# Gameboy_Cartridge.net
KiCad netlist of a schematic drawn in EAGLE
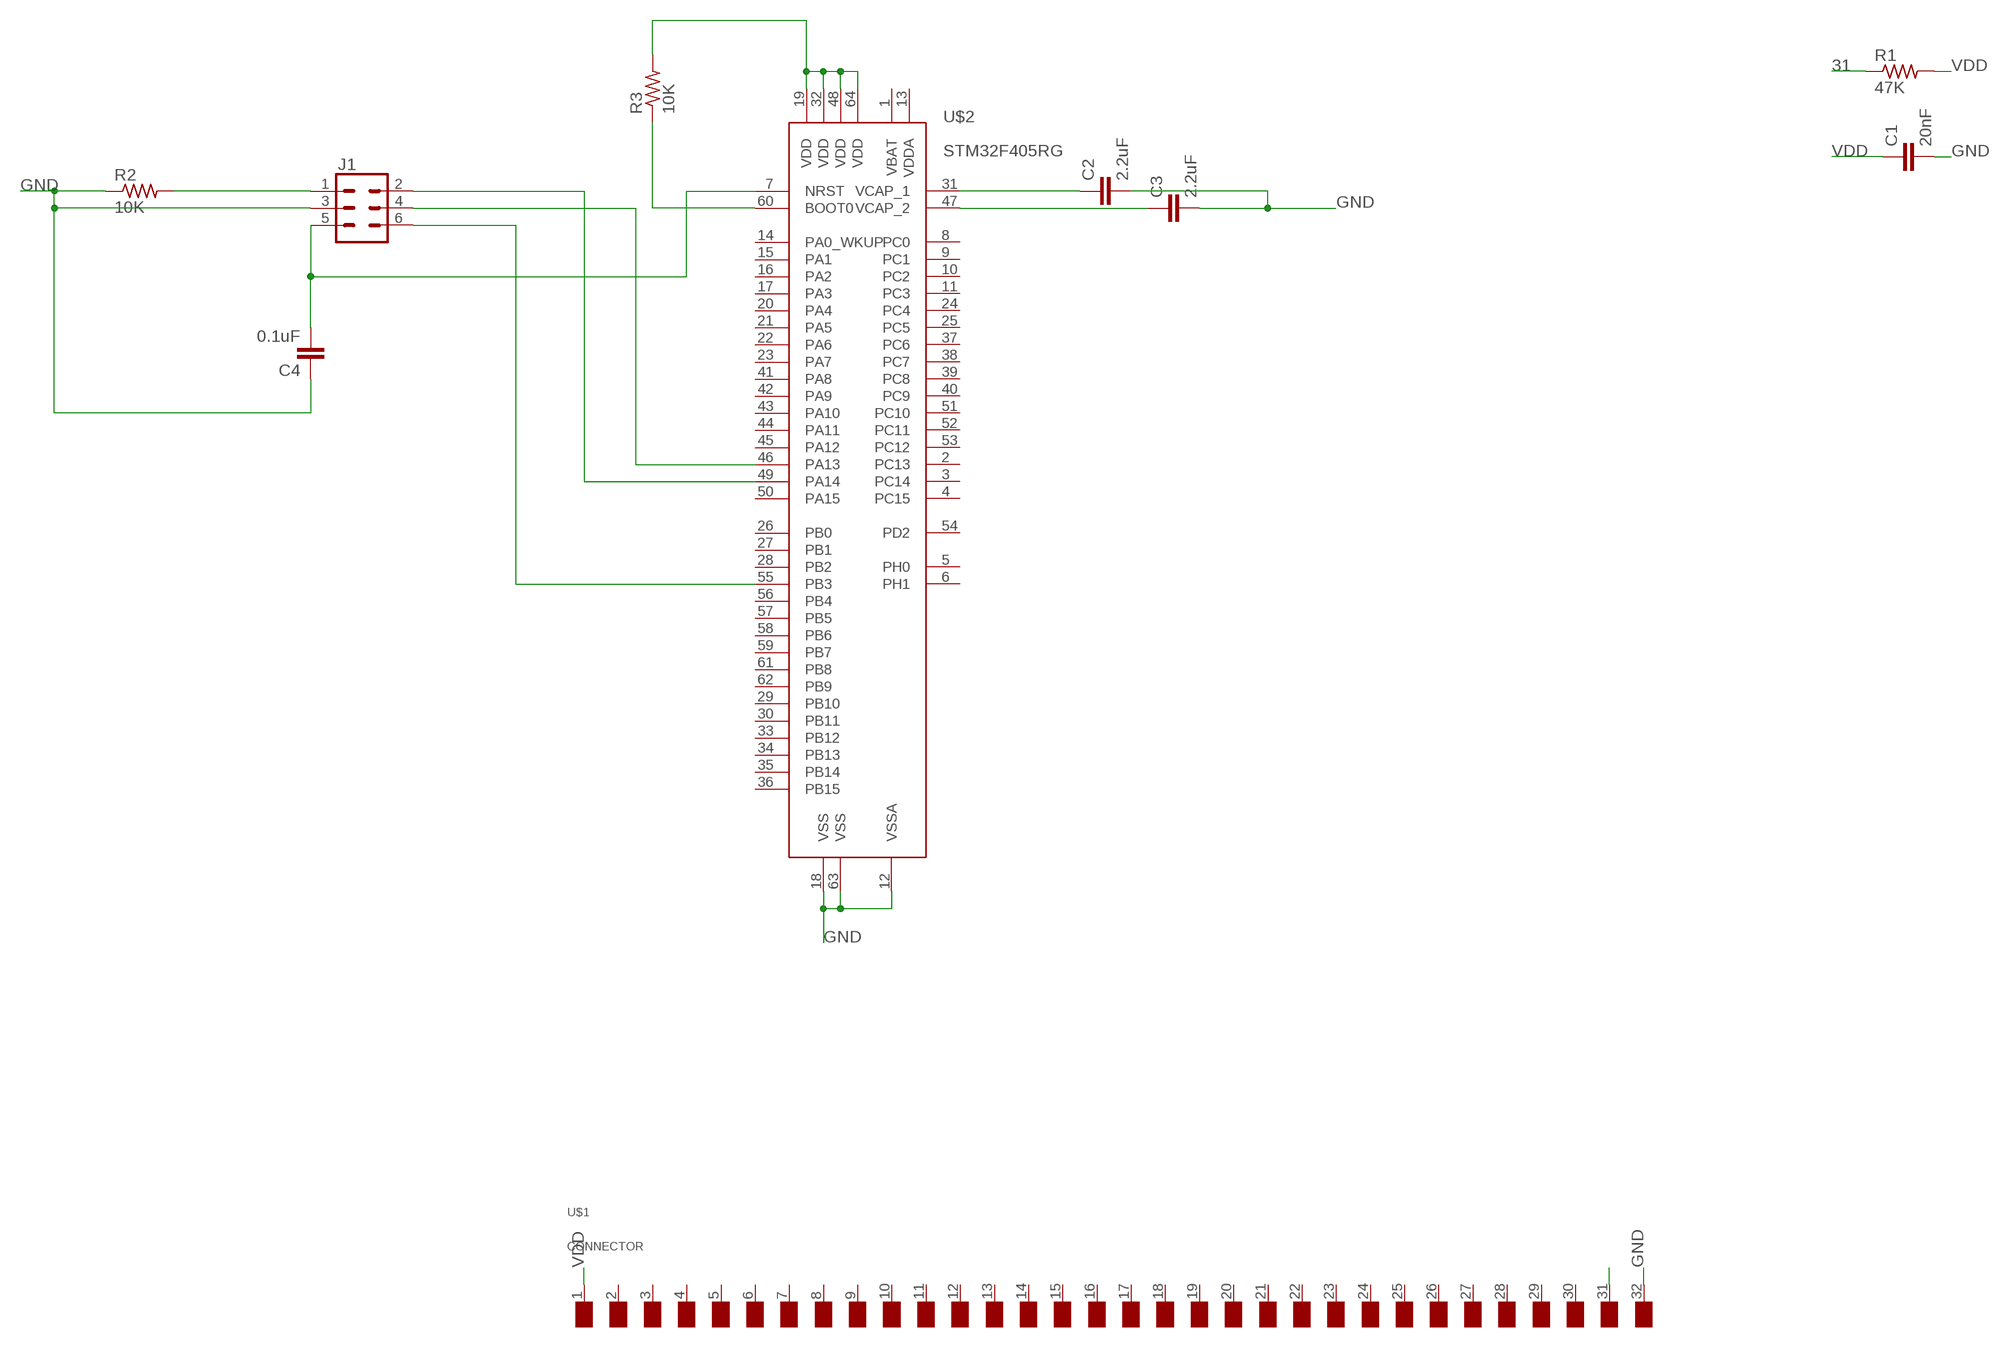
[diagram p0: schematic, sheet 1]

(export (version "E")
  (design (tool "Eeschema 10.0.6"))
  (components
    (comp (ref "C1")
      (value "20nF")
      (footprint "eagle-import:C0805")
      (libsource (lib "eagle-import") (part "C-EUC0805"))
    )
    (comp (ref "C2")
      (value "2.2uF")
      (footprint "eagle-import:C0805")
      (libsource (lib "eagle-import") (part "C-EUC0805"))
    )
    (comp (ref "C3")
      (value "2.2uF")
      (footprint "eagle-import:C0805")
      (libsource (lib "eagle-import") (part "C-EUC0805"))
    )
    (comp (ref "C4")
      (value "0.1uF")
      (footprint "eagle-import:C0805")
      (libsource (lib "eagle-import") (part "C-EUC0805"))
    )
    (comp (ref "J1")
      (value "CONN_03X2FEMALE_SMD")
      (footprint "eagle-import:2X3_SMD")
      (libsource (lib "eagle-import") (part "CONN_03X2FEMALE_SMD"))
    )
    (comp (ref "R1")
      (value "47K")
      (footprint "eagle-import:M0805")
      (libsource (lib "eagle-import") (part "R-US_M0805"))
    )
    (comp (ref "R2")
      (value "10K")
      (footprint "eagle-import:M0805")
      (libsource (lib "eagle-import") (part "R-US_M0805"))
    )
    (comp (ref "R3")
      (value "10K")
      (footprint "eagle-import:M0805")
      (libsource (lib "eagle-import") (part "R-US_M0805"))
    )
    (comp (ref "U$1")
      (value "CONNECTOR")
      (footprint "eagle-import:CONNECTOR")
      (libsource (lib "eagle-import") (part "CONNECTOR"))
    )
    (comp (ref "U$2")
      (value "STM32F405RG")
      (footprint "eagle-import:STM32F405RG")
      (libsource (lib "eagle-import") (part "STM32F405RG"))
    )
  )
  (nets
    (net (code "1") (name "/31") (class "Default")
      (node (ref "R1") (pin "1") (pinfunction "1_1") (pintype "passive"))
      (node (ref "U$1") (pin "31") (pinfunction "VIN_31") (pintype "bidirectional"))
    )
    (net (code "2") (name "/GND") (class "Default")
      (node (ref "C1") (pin "2") (pinfunction "2_2") (pintype "passive"))
      (node (ref "U$1") (pin "32") (pinfunction "GND_32") (pintype "power_in"))
    )
    (net (code "3") (name "/VBAT") (class "Default")
      (node (ref "U$2") (pin "1") (pinfunction "VBAT_1") (pintype "power_in"))
    )
    (net (code "4") (name "/VDD") (class "Default")
      (node (ref "C1") (pin "1") (pinfunction "1_1") (pintype "passive"))
      (node (ref "R1") (pin "2") (pinfunction "2_2") (pintype "passive"))
      (node (ref "U$1") (pin "1") (pinfunction "VDD_1") (pintype "power_in"))
    )
    (net (code "5") (name "/VDDA") (class "Default")
      (node (ref "U$2") (pin "13") (pinfunction "VDDA_13") (pintype "power_in"))
    )
    (net (code "6") (name "Net-(C2-Pad2)") (class "Default")
      (node (ref "C2") (pin "2") (pinfunction "2_2") (pintype "passive"))
      (node (ref "C3") (pin "2") (pinfunction "2_2") (pintype "passive"))
    )
    (net (code "7") (name "Net-(C4-Pad1)") (class "Default")
      (node (ref "C4") (pin "1") (pinfunction "1_1") (pintype "passive"))
      (node (ref "J1") (pin "3") (pinfunction "3_3") (pintype "bidirectional"))
      (node (ref "R2") (pin "1") (pinfunction "1_1") (pintype "passive"))
    )
    (net (code "8") (name "Net-(J1-Pad1)") (class "Default")
      (node (ref "J1") (pin "1") (pinfunction "1_1") (pintype "bidirectional"))
      (node (ref "R2") (pin "2") (pinfunction "2_2") (pintype "passive"))
    )
    (net (code "9") (name "Net-(R3-Pad2)") (class "Default")
      (node (ref "R3") (pin "2") (pinfunction "2_2") (pintype "passive"))
      (node (ref "U$2") (pin "19") (pinfunction "VDD_19") (pintype "power_in"))
      (node (ref "U$2") (pin "32") (pinfunction "VDD_32") (pintype "power_in"))
      (node (ref "U$2") (pin "48") (pinfunction "VDD_48") (pintype "power_in"))
      (node (ref "U$2") (pin "64") (pinfunction "VDD_64") (pintype "power_in"))
    )
    (net (code "10") (name "Net-(U$2-BOOT0)") (class "Default")
      (node (ref "R3") (pin "1") (pinfunction "1_1") (pintype "passive"))
      (node (ref "U$2") (pin "60") (pinfunction "BOOT0_60") (pintype "bidirectional"))
    )
    (net (code "11") (name "Net-(U$2-NRST)") (class "Default")
      (node (ref "C4") (pin "2") (pinfunction "2_2") (pintype "passive"))
      (node (ref "J1") (pin "5") (pinfunction "5_5") (pintype "bidirectional"))
      (node (ref "U$2") (pin "7") (pinfunction "NRST_7") (pintype "bidirectional"))
    )
    (net (code "12") (name "Net-(U$2-PA13)") (class "Default")
      (node (ref "J1") (pin "4") (pinfunction "4_4") (pintype "bidirectional"))
      (node (ref "U$2") (pin "46") (pinfunction "PA13_46") (pintype "bidirectional"))
    )
    (net (code "13") (name "Net-(U$2-PA14)") (class "Default")
      (node (ref "J1") (pin "2") (pinfunction "2_2") (pintype "bidirectional"))
      (node (ref "U$2") (pin "49") (pinfunction "PA14_49") (pintype "bidirectional"))
    )
    (net (code "14") (name "Net-(U$2-PB3)") (class "Default")
      (node (ref "J1") (pin "6") (pinfunction "6_6") (pintype "bidirectional"))
      (node (ref "U$2") (pin "55") (pinfunction "PB3_55") (pintype "bidirectional"))
    )
    (net (code "15") (name "Net-(U$2-VCAP_1)") (class "Default")
      (node (ref "C2") (pin "1") (pinfunction "1_1") (pintype "passive"))
      (node (ref "U$2") (pin "31") (pinfunction "VCAP_1_31") (pintype "bidirectional"))
    )
    (net (code "16") (name "Net-(U$2-VCAP_2)") (class "Default")
      (node (ref "C3") (pin "1") (pinfunction "1_1") (pintype "passive"))
      (node (ref "U$2") (pin "47") (pinfunction "VCAP_2_47") (pintype "bidirectional"))
    )
    (net (code "17") (name "Net-(U$2-VSSA)") (class "Default")
      (node (ref "U$2") (pin "12") (pinfunction "VSSA_12") (pintype "power_in"))
      (node (ref "U$2") (pin "18") (pinfunction "VSS_18") (pintype "power_in"))
      (node (ref "U$2") (pin "63") (pinfunction "VSS_63") (pintype "power_in"))
    )
    (net (code "18") (name "unconnected-(U$1-A0-Pad6)") (class "Default")
      (node (ref "U$1") (pin "6") (pinfunction "A0_6") (pintype "bidirectional"))
    )
    (net (code "19") (name "unconnected-(U$1-A1-Pad7)") (class "Default")
      (node (ref "U$1") (pin "7") (pinfunction "A1_7") (pintype "bidirectional"))
    )
    (net (code "20") (name "unconnected-(U$1-A2-Pad8)") (class "Default")
      (node (ref "U$1") (pin "8") (pinfunction "A2_8") (pintype "bidirectional"))
    )
    (net (code "21") (name "unconnected-(U$1-A3-Pad9)") (class "Default")
      (node (ref "U$1") (pin "9") (pinfunction "A3_9") (pintype "bidirectional"))
    )
    (net (code "22") (name "unconnected-(U$1-A4-Pad10)") (class "Default")
      (node (ref "U$1") (pin "10") (pinfunction "A4_10") (pintype "bidirectional"))
    )
    (net (code "23") (name "unconnected-(U$1-A5-Pad11)") (class "Default")
      (node (ref "U$1") (pin "11") (pinfunction "A5_11") (pintype "bidirectional"))
    )
    (net (code "24") (name "unconnected-(U$1-A6-Pad12)") (class "Default")
      (node (ref "U$1") (pin "12") (pinfunction "A6_12") (pintype "bidirectional"))
    )
    (net (code "25") (name "unconnected-(U$1-A7-Pad13)") (class "Default")
      (node (ref "U$1") (pin "13") (pinfunction "A7_13") (pintype "bidirectional"))
    )
    (net (code "26") (name "unconnected-(U$1-A8-Pad14)") (class "Default")
      (node (ref "U$1") (pin "14") (pinfunction "A8_14") (pintype "bidirectional"))
    )
    (net (code "27") (name "unconnected-(U$1-A9-Pad15)") (class "Default")
      (node (ref "U$1") (pin "15") (pinfunction "A9_15") (pintype "bidirectional"))
    )
    (net (code "28") (name "unconnected-(U$1-A10-Pad16)") (class "Default")
      (node (ref "U$1") (pin "16") (pinfunction "A10_16") (pintype "bidirectional"))
    )
    (net (code "29") (name "unconnected-(U$1-A11-Pad17)") (class "Default")
      (node (ref "U$1") (pin "17") (pinfunction "A11_17") (pintype "bidirectional"))
    )
    (net (code "30") (name "unconnected-(U$1-A12-Pad18)") (class "Default")
      (node (ref "U$1") (pin "18") (pinfunction "A12_18") (pintype "bidirectional"))
    )
    (net (code "31") (name "unconnected-(U$1-A13-Pad19)") (class "Default")
      (node (ref "U$1") (pin "19") (pinfunction "A13_19") (pintype "bidirectional"))
    )
    (net (code "32") (name "unconnected-(U$1-A14-Pad20)") (class "Default")
      (node (ref "U$1") (pin "20") (pinfunction "A14_20") (pintype "bidirectional"))
    )
    (net (code "33") (name "unconnected-(U$1-A15-Pad21)") (class "Default")
      (node (ref "U$1") (pin "21") (pinfunction "A15_21") (pintype "bidirectional"))
    )
    (net (code "34") (name "unconnected-(U$1-D0-Pad22)") (class "Default")
      (node (ref "U$1") (pin "22") (pinfunction "D0_22") (pintype "bidirectional"))
    )
    (net (code "35") (name "unconnected-(U$1-D1-Pad23)") (class "Default")
      (node (ref "U$1") (pin "23") (pinfunction "D1_23") (pintype "bidirectional"))
    )
    (net (code "36") (name "unconnected-(U$1-D2-Pad24)") (class "Default")
      (node (ref "U$1") (pin "24") (pinfunction "D2_24") (pintype "bidirectional"))
    )
    (net (code "37") (name "unconnected-(U$1-D3-Pad25)") (class "Default")
      (node (ref "U$1") (pin "25") (pinfunction "D3_25") (pintype "bidirectional"))
    )
    (net (code "38") (name "unconnected-(U$1-D4-Pad26)") (class "Default")
      (node (ref "U$1") (pin "26") (pinfunction "D4_26") (pintype "bidirectional"))
    )
    (net (code "39") (name "unconnected-(U$1-D5-Pad27)") (class "Default")
      (node (ref "U$1") (pin "27") (pinfunction "D5_27") (pintype "bidirectional"))
    )
    (net (code "40") (name "unconnected-(U$1-D6-Pad28)") (class "Default")
      (node (ref "U$1") (pin "28") (pinfunction "D6_28") (pintype "bidirectional"))
    )
    (net (code "41") (name "unconnected-(U$1-D7-Pad29)") (class "Default")
      (node (ref "U$1") (pin "29") (pinfunction "D7_29") (pintype "bidirectional"))
    )
    (net (code "42") (name "unconnected-(U$1-NC-Pad2)") (class "Default")
      (node (ref "U$1") (pin "2") (pinfunction "NC_2") (pintype "no_connect"))
    )
    (net (code "43") (name "unconnected-(U$1-{slash}RCS-Pad5)") (class "Default")
      (node (ref "U$1") (pin "5") (pinfunction "/RCS_5") (pintype "bidirectional"))
    )
    (net (code "44") (name "unconnected-(U$1-{slash}RD-Pad4)") (class "Default")
      (node (ref "U$1") (pin "4") (pinfunction "/RD_4") (pintype "bidirectional"))
    )
    (net (code "45") (name "unconnected-(U$1-{slash}RS-Pad30)") (class "Default")
      (node (ref "U$1") (pin "30") (pinfunction "/RS_30") (pintype "bidirectional"))
    )
    (net (code "46") (name "unconnected-(U$1-{slash}WR-Pad3)") (class "Default")
      (node (ref "U$1") (pin "3") (pinfunction "/WR_3") (pintype "bidirectional"))
    )
    (net (code "47") (name "unconnected-(U$2-PA0_WKUP-Pad14)") (class "Default")
      (node (ref "U$2") (pin "14") (pinfunction "PA0_WKUP_14") (pintype "bidirectional"))
    )
    (net (code "48") (name "unconnected-(U$2-PA1-Pad15)") (class "Default")
      (node (ref "U$2") (pin "15") (pinfunction "PA1_15") (pintype "bidirectional"))
    )
    (net (code "49") (name "unconnected-(U$2-PA2-Pad16)") (class "Default")
      (node (ref "U$2") (pin "16") (pinfunction "PA2_16") (pintype "bidirectional"))
    )
    (net (code "50") (name "unconnected-(U$2-PA3-Pad17)") (class "Default")
      (node (ref "U$2") (pin "17") (pinfunction "PA3_17") (pintype "bidirectional"))
    )
    (net (code "51") (name "unconnected-(U$2-PA4-Pad20)") (class "Default")
      (node (ref "U$2") (pin "20") (pinfunction "PA4_20") (pintype "bidirectional"))
    )
    (net (code "52") (name "unconnected-(U$2-PA5-Pad21)") (class "Default")
      (node (ref "U$2") (pin "21") (pinfunction "PA5_21") (pintype "bidirectional"))
    )
    (net (code "53") (name "unconnected-(U$2-PA6-Pad22)") (class "Default")
      (node (ref "U$2") (pin "22") (pinfunction "PA6_22") (pintype "bidirectional"))
    )
    (net (code "54") (name "unconnected-(U$2-PA7-Pad23)") (class "Default")
      (node (ref "U$2") (pin "23") (pinfunction "PA7_23") (pintype "bidirectional"))
    )
    (net (code "55") (name "unconnected-(U$2-PA8-Pad41)") (class "Default")
      (node (ref "U$2") (pin "41") (pinfunction "PA8_41") (pintype "bidirectional"))
    )
    (net (code "56") (name "unconnected-(U$2-PA9-Pad42)") (class "Default")
      (node (ref "U$2") (pin "42") (pinfunction "PA9_42") (pintype "bidirectional"))
    )
    (net (code "57") (name "unconnected-(U$2-PA10-Pad43)") (class "Default")
      (node (ref "U$2") (pin "43") (pinfunction "PA10_43") (pintype "bidirectional"))
    )
    (net (code "58") (name "unconnected-(U$2-PA11-Pad44)") (class "Default")
      (node (ref "U$2") (pin "44") (pinfunction "PA11_44") (pintype "bidirectional"))
    )
    (net (code "59") (name "unconnected-(U$2-PA12-Pad45)") (class "Default")
      (node (ref "U$2") (pin "45") (pinfunction "PA12_45") (pintype "bidirectional"))
    )
    (net (code "60") (name "unconnected-(U$2-PA15-Pad50)") (class "Default")
      (node (ref "U$2") (pin "50") (pinfunction "PA15_50") (pintype "bidirectional"))
    )
    (net (code "61") (name "unconnected-(U$2-PB0-Pad26)") (class "Default")
      (node (ref "U$2") (pin "26") (pinfunction "PB0_26") (pintype "bidirectional"))
    )
    (net (code "62") (name "unconnected-(U$2-PB1-Pad27)") (class "Default")
      (node (ref "U$2") (pin "27") (pinfunction "PB1_27") (pintype "bidirectional"))
    )
    (net (code "63") (name "unconnected-(U$2-PB2-Pad28)") (class "Default")
      (node (ref "U$2") (pin "28") (pinfunction "PB2_28") (pintype "bidirectional"))
    )
    (net (code "64") (name "unconnected-(U$2-PB4-Pad56)") (class "Default")
      (node (ref "U$2") (pin "56") (pinfunction "PB4_56") (pintype "bidirectional"))
    )
    (net (code "65") (name "unconnected-(U$2-PB5-Pad57)") (class "Default")
      (node (ref "U$2") (pin "57") (pinfunction "PB5_57") (pintype "bidirectional"))
    )
    (net (code "66") (name "unconnected-(U$2-PB6-Pad58)") (class "Default")
      (node (ref "U$2") (pin "58") (pinfunction "PB6_58") (pintype "bidirectional"))
    )
    (net (code "67") (name "unconnected-(U$2-PB7-Pad59)") (class "Default")
      (node (ref "U$2") (pin "59") (pinfunction "PB7_59") (pintype "bidirectional"))
    )
    (net (code "68") (name "unconnected-(U$2-PB8-Pad61)") (class "Default")
      (node (ref "U$2") (pin "61") (pinfunction "PB8_61") (pintype "bidirectional"))
    )
    (net (code "69") (name "unconnected-(U$2-PB9-Pad62)") (class "Default")
      (node (ref "U$2") (pin "62") (pinfunction "PB9_62") (pintype "bidirectional"))
    )
    (net (code "70") (name "unconnected-(U$2-PB10-Pad29)") (class "Default")
      (node (ref "U$2") (pin "29") (pinfunction "PB10_29") (pintype "bidirectional"))
    )
    (net (code "71") (name "unconnected-(U$2-PB11-Pad30)") (class "Default")
      (node (ref "U$2") (pin "30") (pinfunction "PB11_30") (pintype "bidirectional"))
    )
    (net (code "72") (name "unconnected-(U$2-PB12-Pad33)") (class "Default")
      (node (ref "U$2") (pin "33") (pinfunction "PB12_33") (pintype "bidirectional"))
    )
    (net (code "73") (name "unconnected-(U$2-PB13-Pad34)") (class "Default")
      (node (ref "U$2") (pin "34") (pinfunction "PB13_34") (pintype "bidirectional"))
    )
    (net (code "74") (name "unconnected-(U$2-PB14-Pad35)") (class "Default")
      (node (ref "U$2") (pin "35") (pinfunction "PB14_35") (pintype "bidirectional"))
    )
    (net (code "75") (name "unconnected-(U$2-PB15-Pad36)") (class "Default")
      (node (ref "U$2") (pin "36") (pinfunction "PB15_36") (pintype "bidirectional"))
    )
    (net (code "76") (name "unconnected-(U$2-PC0-Pad8)") (class "Default")
      (node (ref "U$2") (pin "8") (pinfunction "PC0_8") (pintype "bidirectional"))
    )
    (net (code "77") (name "unconnected-(U$2-PC1-Pad9)") (class "Default")
      (node (ref "U$2") (pin "9") (pinfunction "PC1_9") (pintype "bidirectional"))
    )
    (net (code "78") (name "unconnected-(U$2-PC2-Pad10)") (class "Default")
      (node (ref "U$2") (pin "10") (pinfunction "PC2_10") (pintype "bidirectional"))
    )
    (net (code "79") (name "unconnected-(U$2-PC3-Pad11)") (class "Default")
      (node (ref "U$2") (pin "11") (pinfunction "PC3_11") (pintype "bidirectional"))
    )
    (net (code "80") (name "unconnected-(U$2-PC4-Pad24)") (class "Default")
      (node (ref "U$2") (pin "24") (pinfunction "PC4_24") (pintype "bidirectional"))
    )
    (net (code "81") (name "unconnected-(U$2-PC5-Pad25)") (class "Default")
      (node (ref "U$2") (pin "25") (pinfunction "PC5_25") (pintype "bidirectional"))
    )
    (net (code "82") (name "unconnected-(U$2-PC6-Pad37)") (class "Default")
      (node (ref "U$2") (pin "37") (pinfunction "PC6_37") (pintype "bidirectional"))
    )
    (net (code "83") (name "unconnected-(U$2-PC7-Pad38)") (class "Default")
      (node (ref "U$2") (pin "38") (pinfunction "PC7_38") (pintype "bidirectional"))
    )
    (net (code "84") (name "unconnected-(U$2-PC8-Pad39)") (class "Default")
      (node (ref "U$2") (pin "39") (pinfunction "PC8_39") (pintype "bidirectional"))
    )
    (net (code "85") (name "unconnected-(U$2-PC9-Pad40)") (class "Default")
      (node (ref "U$2") (pin "40") (pinfunction "PC9_40") (pintype "bidirectional"))
    )
    (net (code "86") (name "unconnected-(U$2-PC10-Pad51)") (class "Default")
      (node (ref "U$2") (pin "51") (pinfunction "PC10_51") (pintype "bidirectional"))
    )
    (net (code "87") (name "unconnected-(U$2-PC11-Pad52)") (class "Default")
      (node (ref "U$2") (pin "52") (pinfunction "PC11_52") (pintype "bidirectional"))
    )
    (net (code "88") (name "unconnected-(U$2-PC12-Pad53)") (class "Default")
      (node (ref "U$2") (pin "53") (pinfunction "PC12_53") (pintype "bidirectional"))
    )
    (net (code "89") (name "unconnected-(U$2-PC13-Pad2)") (class "Default")
      (node (ref "U$2") (pin "2") (pinfunction "PC13_2") (pintype "bidirectional"))
    )
    (net (code "90") (name "unconnected-(U$2-PC14-Pad3)") (class "Default")
      (node (ref "U$2") (pin "3") (pinfunction "PC14_3") (pintype "bidirectional"))
    )
    (net (code "91") (name "unconnected-(U$2-PC15-Pad4)") (class "Default")
      (node (ref "U$2") (pin "4") (pinfunction "PC15_4") (pintype "bidirectional"))
    )
    (net (code "92") (name "unconnected-(U$2-PD2-Pad54)") (class "Default")
      (node (ref "U$2") (pin "54") (pinfunction "PD2_54") (pintype "bidirectional"))
    )
    (net (code "93") (name "unconnected-(U$2-PH0-Pad5)") (class "Default")
      (node (ref "U$2") (pin "5") (pinfunction "PH0_5") (pintype "bidirectional"))
    )
    (net (code "94") (name "unconnected-(U$2-PH1-Pad6)") (class "Default")
      (node (ref "U$2") (pin "6") (pinfunction "PH1_6") (pintype "bidirectional"))
    )
  )
)
